# SparkFun_GPS_ZED-F9K_uHat.net
KiCad netlist of a schematic drawn in EAGLE
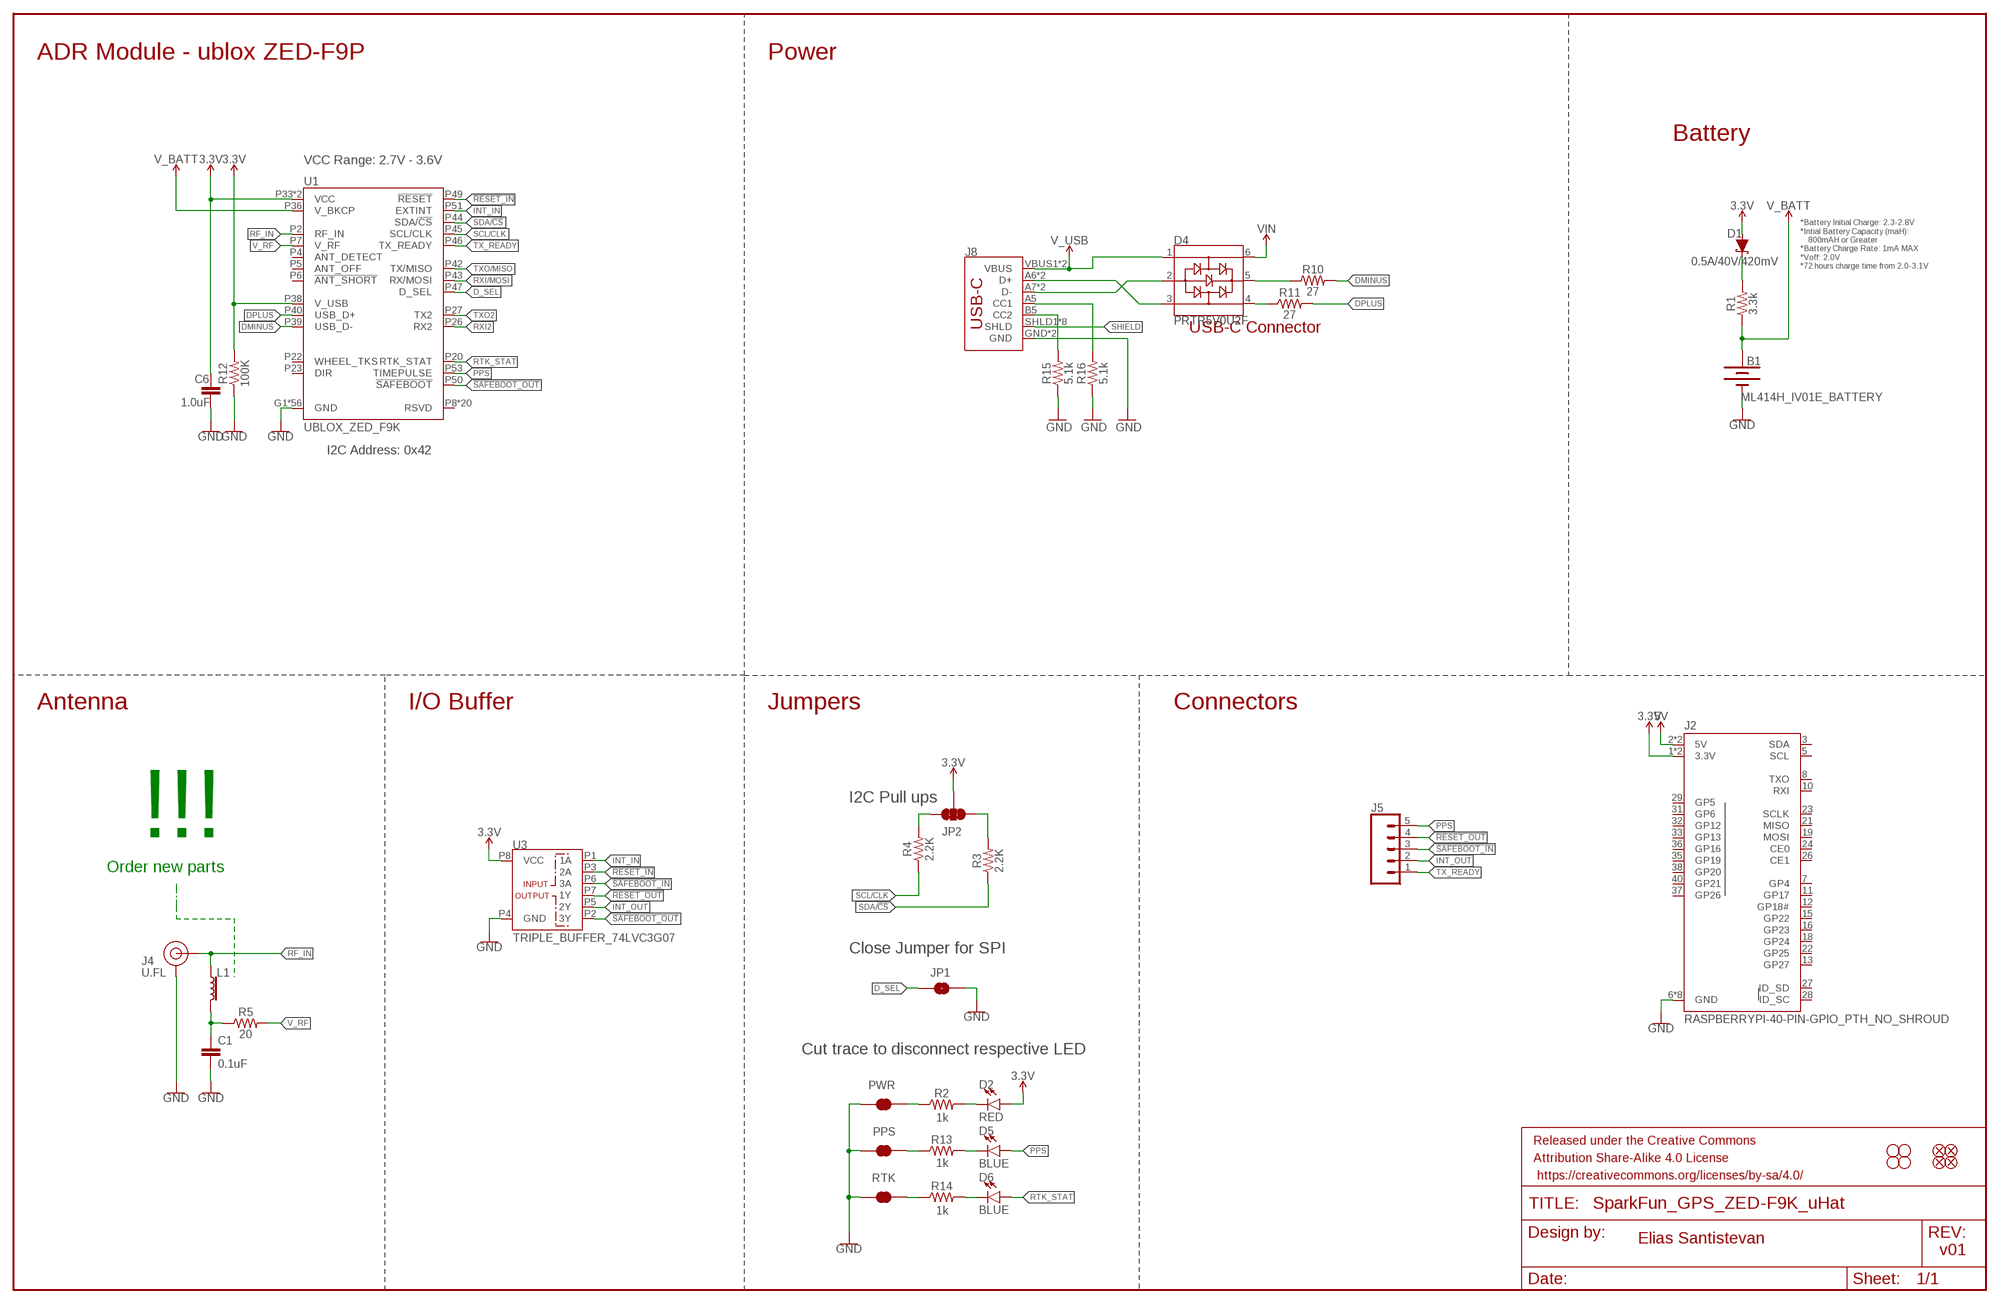
[diagram p0: schematic, sheet 1]

(export (version "E")
  (design (tool "Eeschema 10.0.6"))
  (components
    (comp (ref "B1")
      (value "ML414H_IV01E_BATTERY")
      (footprint "eagle-import:ML414H_IV01E")
      (libsource (lib "eagle-import") (part "ML414H_IV01E_BATTERY"))
    )
    (comp (ref "C1")
      (value "0.1uF")
      (footprint "eagle-import:0402")
      (libsource (lib "eagle-import") (part "0.1UF-0402-16V-10%"))
    )
    (comp (ref "C6")
      (value "1.0uF")
      (footprint "eagle-import:0402")
      (libsource (lib "eagle-import") (part "1.0UF-0402-16V-10%"))
    )
    (comp (ref "D1")
      (value "0.5A/40V/420mV")
      (footprint "eagle-import:SOD-323")
      (libsource (lib "eagle-import") (part "DIODE-SCHOTTKY-PMEG4005EJ"))
    )
    (comp (ref "D2")
      (value "RED")
      (footprint "eagle-import:LED-0603")
      (libsource (lib "eagle-import") (part "LED-RED0603"))
    )
    (comp (ref "D4")
      (value "PRTR5V0U2F")
      (footprint "eagle-import:SOT886")
      (libsource (lib "eagle-import") (part "PRTR5V0U2F"))
    )
    (comp (ref "D5")
      (value "BLUE")
      (footprint "eagle-import:LED-0603")
      (libsource (lib "eagle-import") (part "LED-BLUE0603"))
    )
    (comp (ref "D6")
      (value "BLUE")
      (footprint "eagle-import:LED-0603")
      (libsource (lib "eagle-import") (part "LED-BLUE0603"))
    )
    (comp (ref "FD9")
      (value "FIDUCIALUFIDUCIAL")
      (footprint "eagle-import:FIDUCIAL-MICRO")
      (libsource (lib "eagle-import") (part "FIDUCIALUFIDUCIAL"))
    )
    (comp (ref "FD10")
      (value "FIDUCIALUFIDUCIAL")
      (footprint "eagle-import:FIDUCIAL-MICRO")
      (libsource (lib "eagle-import") (part "FIDUCIALUFIDUCIAL"))
    )
    (comp (ref "FD11")
      (value "FIDUCIALUFIDUCIAL")
      (footprint "eagle-import:FIDUCIAL-MICRO")
      (libsource (lib "eagle-import") (part "FIDUCIALUFIDUCIAL"))
    )
    (comp (ref "FD12")
      (value "FIDUCIALUFIDUCIAL")
      (footprint "eagle-import:FIDUCIAL-MICRO")
      (libsource (lib "eagle-import") (part "FIDUCIALUFIDUCIAL"))
    )
    (comp (ref "FRAME2")
      (value "FRAME-LEDGER")
      (footprint "eagle-import:CREATIVE_COMMONS")
      (libsource (lib "eagle-import") (part "FRAME-LEDGER"))
    )
    (comp (ref "H9")
      (value "STAND-OFFTIGHT")
      (footprint "eagle-import:STAND-OFF-TIGHT")
      (libsource (lib "eagle-import") (part "STAND-OFFTIGHT"))
    )
    (comp (ref "H10")
      (value "STAND-OFFTIGHT")
      (footprint "eagle-import:STAND-OFF-TIGHT")
      (libsource (lib "eagle-import") (part "STAND-OFFTIGHT"))
    )
    (comp (ref "H11")
      (value "STAND-OFFTIGHT")
      (footprint "eagle-import:STAND-OFF-TIGHT")
      (libsource (lib "eagle-import") (part "STAND-OFFTIGHT"))
    )
    (comp (ref "H12")
      (value "STAND-OFFTIGHT")
      (footprint "eagle-import:STAND-OFF-TIGHT")
      (libsource (lib "eagle-import") (part "STAND-OFFTIGHT"))
    )
    (comp (ref "J2")
      (value "RASPBERRYPI-40-PIN-GPIO_PTH_NO_SHROUD")
      (footprint "eagle-import:2X20")
      (libsource (lib "eagle-import") (part "RASPBERRYPI-40-PIN-GPIO_PTH_NO_SHROUD"))
    )
    (comp (ref "J4")
      (value "U.FL")
      (footprint "eagle-import:U.FL")
      (libsource (lib "eagle-import") (part "U.FL2PIN"))
    )
    (comp (ref "J5")
      (value "CONN_05NO_SILK")
      (footprint "eagle-import:1X05_NO_SILK")
      (libsource (lib "eagle-import") (part "CONN_05NO_SILK"))
    )
    (comp (ref "J8")
      (value "USB_C2-LAYER")
      (footprint "eagle-import:USB-C-16P")
      (libsource (lib "eagle-import") (part "USB_C2-LAYER"))
    )
    (comp (ref "JP1")
      (value "JUMPER-SMT_2_NO_SILK")
      (footprint "eagle-import:SMT-JUMPER_2_NO_SILK")
      (libsource (lib "eagle-import") (part "JUMPER-SMT_2_NO_SILK"))
    )
    (comp (ref "JP2")
      (value "JUMPER-SMT_3_2-NC_TRACE_SILK")
      (footprint "eagle-import:SMT-JUMPER_3_2-NC_TRACE_SILK")
      (libsource (lib "eagle-import") (part "JUMPER-SMT_3_2-NC_TRACE_SILK"))
    )
    (comp (ref "L1")
      (value "3.9NH")
      (footprint "eagle-import:0402")
      (fields (field (name "MFG_PART") "BLM15HB121SN1D"))
      (libsource (lib "eagle-import") (part "FERRITE_BEAD-120_OHM-0402"))
    )
    (comp (ref "PPS")
      (value "JUMPER-SMT_2_NC_TRACE_SILK")
      (footprint "eagle-import:SMT-JUMPER_2_NC_TRACE_SILK")
      (libsource (lib "eagle-import") (part "JUMPER-SMT_2_NC_TRACE_SILK"))
    )
    (comp (ref "PWR")
      (value "JUMPER-SMT_2_NC_TRACE_SILK")
      (footprint "eagle-import:SMT-JUMPER_2_NC_TRACE_SILK")
      (libsource (lib "eagle-import") (part "JUMPER-SMT_2_NC_TRACE_SILK"))
    )
    (comp (ref "R1")
      (value "3.3k")
      (footprint "eagle-import:0603")
      (libsource (lib "eagle-import") (part "3.3KOHM-0603-1/10W-1%"))
    )
    (comp (ref "R2")
      (value "1KOHM-0402-1/16W-1%")
      (footprint "eagle-import:0402")
      (libsource (lib "eagle-import") (part "1KOHM-0402-1/16W-1%"))
    )
    (comp (ref "R3")
      (value "2.2K")
      (footprint "eagle-import:0402")
      (libsource (lib "eagle-import") (part "2.2KOHM-0402-1/16W-1%"))
    )
    (comp (ref "R4")
      (value "2.2K")
      (footprint "eagle-import:0402")
      (libsource (lib "eagle-import") (part "2.2KOHM-0402-1/16W-1%"))
    )
    (comp (ref "R5")
      (value "20")
      (footprint "eagle-import:0603")
      (libsource (lib "eagle-import") (part "20OHM-0603-1/10W-1%"))
    )
    (comp (ref "R10")
      (value "27")
      (footprint "eagle-import:0603")
      (libsource (lib "eagle-import") (part "27OHM-0603-1/10W-1%"))
    )
    (comp (ref "R11")
      (value "27")
      (footprint "eagle-import:0603")
      (libsource (lib "eagle-import") (part "27OHM-0603-1/10W-1%"))
    )
    (comp (ref "R12")
      (value "100K")
      (footprint "eagle-import:0402")
      (libsource (lib "eagle-import") (part "100KOHM-0402-1/16W-1%"))
    )
    (comp (ref "R13")
      (value "1KOHM-0402-1/16W-1%")
      (footprint "eagle-import:0402")
      (libsource (lib "eagle-import") (part "1KOHM-0402-1/16W-1%"))
    )
    (comp (ref "R14")
      (value "1KOHM-0402-1/16W-1%")
      (footprint "eagle-import:0402")
      (libsource (lib "eagle-import") (part "1KOHM-0402-1/16W-1%"))
    )
    (comp (ref "R15")
      (value "5.1k")
      (footprint "eagle-import:0402")
      (libsource (lib "eagle-import") (part "5.1KOHM-0402-1/16W-1%"))
    )
    (comp (ref "R16")
      (value "5.1k")
      (footprint "eagle-import:0402")
      (libsource (lib "eagle-import") (part "5.1KOHM-0402-1/16W-1%"))
    )
    (comp (ref "RTK")
      (value "JUMPER-SMT_2_NC_TRACE_SILK")
      (footprint "eagle-import:SMT-JUMPER_2_NC_TRACE_SILK")
      (libsource (lib "eagle-import") (part "JUMPER-SMT_2_NC_TRACE_SILK"))
    )
    (comp (ref "U1")
      (value "UBLOX_ZED_F9K")
      (footprint "eagle-import:UBLOX_ZED_F9K")
      (libsource (lib "eagle-import") (part "UBLOX_ZED_F9K"))
    )
    (comp (ref "U3")
      (value "TRIPLE_BUFFER_74LVC3G07")
      (footprint "eagle-import:SOP_8-PIN")
      (libsource (lib "eagle-import") (part "TRIPLE_BUFFER_74LVC3G07"))
    )
  )
  (nets
    (net (code "1") (name "/SDA{slash}~{CS}") (class "Default")
      (node (ref "R3") (pin "1") (pinfunction "1_1") (pintype "passive"))
      (node (ref "U1") (pin "P44") (pinfunction "SDA/~{CS}_P44") (pintype "bidirectional"))
    )
    (net (code "2") (name "/~{RESET_IN}") (class "Default")
      (node (ref "U1") (pin "P49") (pinfunction "~{RESET}_P49") (pintype "bidirectional"))
      (node (ref "U3") (pin "P3") (pinfunction "2A_P3") (pintype "bidirectional"))
    )
    (net (code "3") (name "/~{RESET_OUT}") (class "Default")
      (node (ref "J5") (pin "4") (pinfunction "4_4") (pintype "passive"))
      (node (ref "U3") (pin "P7") (pinfunction "1Y_P7") (pintype "bidirectional"))
    )
    (net (code "4") (name "/~{SAFEBOOT_IN}") (class "Default")
      (node (ref "J5") (pin "3") (pinfunction "3_3") (pintype "passive"))
      (node (ref "U3") (pin "P6") (pinfunction "3A_P6") (pintype "bidirectional"))
    )
    (net (code "5") (name "/~{SAFEBOOT_OUT}") (class "Default")
      (node (ref "U1") (pin "P50") (pinfunction "~{SAFEBOOT}_P50") (pintype "input"))
      (node (ref "U3") (pin "P2") (pinfunction "3Y_P2") (pintype "bidirectional"))
    )
    (net (code "6") (name "3.3V") (class "Default")
      (node (ref "C6") (pin "1") (pinfunction "1_1") (pintype "passive"))
      (node (ref "D1") (pin "A") (pinfunction "A_A") (pintype "passive"))
      (node (ref "D2") (pin "A") (pinfunction "A_A") (pintype "passive"))
      (node (ref "J2") (pin "1") (pinfunction "3.3V_1") (pintype "power_in"))
      (node (ref "J2") (pin "17") (pinfunction "3.3V_17") (pintype "power_in"))
      (node (ref "JP2") (pin "2") (pinfunction "2_2") (pintype "passive"))
      (node (ref "R12") (pin "2") (pinfunction "2_2") (pintype "passive"))
      (node (ref "U1") (pin "P33") (pinfunction "VCC_P33") (pintype "power_in"))
      (node (ref "U1") (pin "P34") (pinfunction "VCC_P34") (pintype "power_in"))
      (node (ref "U1") (pin "P38") (pinfunction "V_USB_P38") (pintype "power_in"))
      (node (ref "U3") (pin "P8") (pinfunction "VCC_P8") (pintype "power_in"))
    )
    (net (code "7") (name "5V") (class "Default")
      (node (ref "J2") (pin "2") (pinfunction "5V_2") (pintype "power_in"))
      (node (ref "J2") (pin "4") (pinfunction "5V_4") (pintype "power_in"))
    )
    (net (code "8") (name "DMINUS") (class "Default")
      (node (ref "R10") (pin "2") (pinfunction "2_2") (pintype "passive"))
      (node (ref "U1") (pin "P39") (pinfunction "USB_D-_P39") (pintype "bidirectional"))
    )
    (net (code "9") (name "DPLUS") (class "Default")
      (node (ref "R11") (pin "2") (pinfunction "2_2") (pintype "passive"))
      (node (ref "U1") (pin "P40") (pinfunction "USB_D+_P40") (pintype "bidirectional"))
    )
    (net (code "10") (name "D_SEL") (class "Default")
      (node (ref "JP1") (pin "1") (pinfunction "1_1") (pintype "passive"))
      (node (ref "U1") (pin "P47") (pinfunction "D_SEL_P47") (pintype "bidirectional"))
    )
    (net (code "11") (name "GND") (class "Default")
      (node (ref "B1") (pin "-") (pinfunction "-_-") (pintype "power_in"))
      (node (ref "C1") (pin "2") (pinfunction "2_2") (pintype "passive"))
      (node (ref "C6") (pin "2") (pinfunction "2_2") (pintype "passive"))
      (node (ref "J2") (pin "14") (pinfunction "GND_14") (pintype "power_in"))
      (node (ref "J2") (pin "20") (pinfunction "GND_20") (pintype "power_in"))
      (node (ref "J2") (pin "25") (pinfunction "GND_25") (pintype "power_in"))
      (node (ref "J2") (pin "30") (pinfunction "GND_30") (pintype "power_in"))
      (node (ref "J2") (pin "34") (pinfunction "GND_34") (pintype "power_in"))
      (node (ref "J2") (pin "39") (pinfunction "GND_39") (pintype "power_in"))
      (node (ref "J2") (pin "6") (pinfunction "GND_6") (pintype "power_in"))
      (node (ref "J2") (pin "9") (pinfunction "GND_9") (pintype "power_in"))
      (node (ref "J4") (pin "1") (pinfunction "GND_1") (pintype "bidirectional"))
      (node (ref "J4") (pin "2") (pinfunction "GND_2") (pintype "bidirectional"))
      (node (ref "J8") (pin "GND") (pinfunction "GND_GND") (pintype "bidirectional"))
      (node (ref "J8") (pin "GND2") (pinfunction "GND_GND2") (pintype "bidirectional"))
      (node (ref "JP1") (pin "2") (pinfunction "2_2") (pintype "passive"))
      (node (ref "PPS") (pin "1") (pinfunction "1_1") (pintype "passive"))
      (node (ref "PWR") (pin "1") (pinfunction "1_1") (pintype "passive"))
      (node (ref "R12") (pin "1") (pinfunction "1_1") (pintype "passive"))
      (node (ref "R15") (pin "1") (pinfunction "1_1") (pintype "passive"))
      (node (ref "R16") (pin "1") (pinfunction "1_1") (pintype "passive"))
      (node (ref "RTK") (pin "1") (pinfunction "1_1") (pintype "passive"))
      (node (ref "U1") (pin "G1") (pinfunction "GND_G1") (pintype "power_in"))
      (node (ref "U1") (pin "G10") (pinfunction "GND_G10") (pintype "power_in"))
      (node (ref "U1") (pin "G11") (pinfunction "GND_G11") (pintype "power_in"))
      (node (ref "U1") (pin "G12") (pinfunction "GND_G12") (pintype "power_in"))
      (node (ref "U1") (pin "G13") (pinfunction "GND_G13") (pintype "power_in"))
      (node (ref "U1") (pin "G14") (pinfunction "GND_G14") (pintype "power_in"))
      (node (ref "U1") (pin "G15") (pinfunction "GND_G15") (pintype "power_in"))
      (node (ref "U1") (pin "G16") (pinfunction "GND_G16") (pintype "power_in"))
      (node (ref "U1") (pin "G17") (pinfunction "GND_G17") (pintype "power_in"))
      (node (ref "U1") (pin "G18") (pinfunction "GND_G18") (pintype "power_in"))
      (node (ref "U1") (pin "G19") (pinfunction "GND_G19") (pintype "power_in"))
      (node (ref "U1") (pin "G2") (pinfunction "GND_G2") (pintype "power_in"))
      (node (ref "U1") (pin "G20") (pinfunction "GND_G20") (pintype "power_in"))
      (node (ref "U1") (pin "G21") (pinfunction "GND_G21") (pintype "power_in"))
      (node (ref "U1") (pin "G22") (pinfunction "GND_G22") (pintype "power_in"))
      (node (ref "U1") (pin "G23") (pinfunction "GND_G23") (pintype "power_in"))
      (node (ref "U1") (pin "G24") (pinfunction "GND_G24") (pintype "power_in"))
      (node (ref "U1") (pin "G25") (pinfunction "GND_G25") (pintype "power_in"))
      (node (ref "U1") (pin "G26") (pinfunction "GND_G26") (pintype "power_in"))
      (node (ref "U1") (pin "G27") (pinfunction "GND_G27") (pintype "power_in"))
      (node (ref "U1") (pin "G28") (pinfunction "GND_G28") (pintype "power_in"))
      (node (ref "U1") (pin "G29") (pinfunction "GND_G29") (pintype "power_in"))
      (node (ref "U1") (pin "G3") (pinfunction "GND_G3") (pintype "power_in"))
      (node (ref "U1") (pin "G30") (pinfunction "GND_G30") (pintype "power_in"))
      (node (ref "U1") (pin "G31") (pinfunction "GND_G31") (pintype "power_in"))
      (node (ref "U1") (pin "G32") (pinfunction "GND_G32") (pintype "power_in"))
      (node (ref "U1") (pin "G33") (pinfunction "GND_G33") (pintype "power_in"))
      (node (ref "U1") (pin "G34") (pinfunction "GND_G34") (pintype "power_in"))
      (node (ref "U1") (pin "G35") (pinfunction "GND_G35") (pintype "power_in"))
      (node (ref "U1") (pin "G36") (pinfunction "GND_G36") (pintype "power_in"))
      (node (ref "U1") (pin "G37") (pinfunction "GND_G37") (pintype "power_in"))
      (node (ref "U1") (pin "G38") (pinfunction "GND_G38") (pintype "power_in"))
      (node (ref "U1") (pin "G39") (pinfunction "GND_G39") (pintype "power_in"))
      (node (ref "U1") (pin "G4") (pinfunction "GND_G4") (pintype "power_in"))
      (node (ref "U1") (pin "G40") (pinfunction "GND_G40") (pintype "power_in"))
      (node (ref "U1") (pin "G41") (pinfunction "GND_G41") (pintype "power_in"))
      (node (ref "U1") (pin "G42") (pinfunction "GND_G42") (pintype "power_in"))
      (node (ref "U1") (pin "G43") (pinfunction "GND_G43") (pintype "power_in"))
      (node (ref "U1") (pin "G44") (pinfunction "GND_G44") (pintype "power_in"))
      (node (ref "U1") (pin "G45") (pinfunction "GND_G45") (pintype "power_in"))
      (node (ref "U1") (pin "G46") (pinfunction "GND_G46") (pintype "power_in"))
      (node (ref "U1") (pin "G47") (pinfunction "GND_G47") (pintype "power_in"))
      (node (ref "U1") (pin "G48") (pinfunction "GND_G48") (pintype "power_in"))
      (node (ref "U1") (pin "G5") (pinfunction "GND_G5") (pintype "power_in"))
      (node (ref "U1") (pin "G6") (pinfunction "GND_G6") (pintype "power_in"))
      (node (ref "U1") (pin "G7") (pinfunction "GND_G7") (pintype "power_in"))
      (node (ref "U1") (pin "G8") (pinfunction "GND_G8") (pintype "power_in"))
      (node (ref "U1") (pin "G9") (pinfunction "GND_G9") (pintype "power_in"))
      (node (ref "U1") (pin "P1") (pinfunction "GND_P1") (pintype "power_in"))
      (node (ref "U1") (pin "P12") (pinfunction "GND_P12") (pintype "power_in"))
      (node (ref "U1") (pin "P14") (pinfunction "GND_P14") (pintype "power_in"))
      (node (ref "U1") (pin "P3") (pinfunction "GND_P3") (pintype "power_in"))
      (node (ref "U1") (pin "P32") (pinfunction "GND_P32") (pintype "power_in"))
      (node (ref "U1") (pin "P37") (pinfunction "GND_P37") (pintype "power_in"))
      (node (ref "U1") (pin "P41") (pinfunction "GND_P41") (pintype "power_in"))
      (node (ref "U1") (pin "P48") (pinfunction "GND_P48") (pintype "power_in"))
      (node (ref "U3") (pin "P4") (pinfunction "GND_P4") (pintype "power_in"))
    )
    (net (code "12") (name "INT_IN") (class "Default")
      (node (ref "U1") (pin "P51") (pinfunction "EXTINT_P51") (pintype "bidirectional"))
      (node (ref "U3") (pin "P1") (pinfunction "1A_P1") (pintype "bidirectional"))
    )
    (net (code "13") (name "INT_OUT") (class "Default")
      (node (ref "J5") (pin "2") (pinfunction "2_2") (pintype "passive"))
      (node (ref "U3") (pin "P5") (pinfunction "2Y_P5") (pintype "bidirectional"))
    )
    (net (code "14") (name "Net-(C1-Pad1)") (class "Default")
      (node (ref "C1") (pin "1") (pinfunction "1_1") (pintype "passive"))
      (node (ref "L1") (pin "2") (pinfunction "2_2") (pintype "passive"))
      (node (ref "R5") (pin "1") (pinfunction "1_1") (pintype "passive"))
    )
    (net (code "15") (name "Net-(D1-PadC)") (class "Default")
      (node (ref "D1") (pin "C") (pinfunction "C_C") (pintype "passive"))
      (node (ref "R1") (pin "2") (pinfunction "2_2") (pintype "passive"))
    )
    (net (code "16") (name "Net-(D2-PadC)") (class "Default")
      (node (ref "D2") (pin "C") (pinfunction "C_C") (pintype "passive"))
      (node (ref "R2") (pin "2") (pinfunction "2_2") (pintype "passive"))
    )
    (net (code "17") (name "Net-(D4-Pad2)") (class "Default")
      (node (ref "D4") (pin "2") (pinfunction "2_2") (pintype "bidirectional"))
      (node (ref "J8") (pin "A7") (pinfunction "D-_A7") (pintype "bidirectional"))
      (node (ref "J8") (pin "B7") (pinfunction "D-_B7") (pintype "bidirectional"))
    )
    (net (code "18") (name "Net-(D4-Pad3)") (class "Default")
      (node (ref "D4") (pin "3") (pinfunction "3_3") (pintype "bidirectional"))
      (node (ref "J8") (pin "A6") (pinfunction "D+_A6") (pintype "bidirectional"))
      (node (ref "J8") (pin "B6") (pinfunction "D+_B6") (pintype "bidirectional"))
    )
    (net (code "19") (name "Net-(D4-Pad4)") (class "Default")
      (node (ref "D4") (pin "4") (pinfunction "4_4") (pintype "bidirectional"))
      (node (ref "R11") (pin "1") (pinfunction "1_1") (pintype "passive"))
    )
    (net (code "20") (name "Net-(D4-Pad5)") (class "Default")
      (node (ref "D4") (pin "5") (pinfunction "5_5") (pintype "bidirectional"))
      (node (ref "R10") (pin "1") (pinfunction "1_1") (pintype "passive"))
    )
    (net (code "21") (name "Net-(D5-PadC)") (class "Default")
      (node (ref "D5") (pin "C") (pinfunction "C_C") (pintype "passive"))
      (node (ref "R13") (pin "2") (pinfunction "2_2") (pintype "passive"))
    )
    (net (code "22") (name "Net-(D6-PadC)") (class "Default")
      (node (ref "D6") (pin "C") (pinfunction "C_C") (pintype "passive"))
      (node (ref "R14") (pin "2") (pinfunction "2_2") (pintype "passive"))
    )
    (net (code "23") (name "Net-(J8-CC1)") (class "Default")
      (node (ref "J8") (pin "A5") (pinfunction "CC1_A5") (pintype "bidirectional"))
      (node (ref "R16") (pin "2") (pinfunction "2_2") (pintype "passive"))
    )
    (net (code "24") (name "Net-(J8-CC2)") (class "Default")
      (node (ref "J8") (pin "B5") (pinfunction "CC2_B5") (pintype "bidirectional"))
      (node (ref "R15") (pin "2") (pinfunction "2_2") (pintype "passive"))
    )
    (net (code "25") (name "Net-(JP2-Pad1)") (class "Default")
      (node (ref "JP2") (pin "1") (pinfunction "1_1") (pintype "passive"))
      (node (ref "R3") (pin "2") (pinfunction "2_2") (pintype "passive"))
    )
    (net (code "26") (name "Net-(JP2-Pad3)") (class "Default")
      (node (ref "JP2") (pin "3") (pinfunction "3_3") (pintype "passive"))
      (node (ref "R4") (pin "2") (pinfunction "2_2") (pintype "passive"))
    )
    (net (code "27") (name "Net-(PPS-Pad2)") (class "Default")
      (node (ref "PPS") (pin "2") (pinfunction "2_2") (pintype "passive"))
      (node (ref "R13") (pin "1") (pinfunction "1_1") (pintype "passive"))
    )
    (net (code "28") (name "Net-(PWR-Pad2)") (class "Default")
      (node (ref "PWR") (pin "2") (pinfunction "2_2") (pintype "passive"))
      (node (ref "R2") (pin "1") (pinfunction "1_1") (pintype "passive"))
    )
    (net (code "29") (name "Net-(R14-Pad1)") (class "Default")
      (node (ref "R14") (pin "1") (pinfunction "1_1") (pintype "passive"))
      (node (ref "RTK") (pin "2") (pinfunction "2_2") (pintype "passive"))
    )
    (net (code "30") (name "PPS") (class "Default")
      (node (ref "D5") (pin "A") (pinfunction "A_A") (pintype "passive"))
      (node (ref "J5") (pin "5") (pinfunction "5_5") (pintype "passive"))
      (node (ref "U1") (pin "P53") (pinfunction "TIMEPULSE_P53") (pintype "output"))
    )
    (net (code "31") (name "RF_IN") (class "Default")
      (node (ref "J4") (pin "FEED") (pinfunction "SIGNAL_FEED") (pintype "bidirectional"))
      (node (ref "L1") (pin "1") (pinfunction "1_1") (pintype "passive"))
      (node (ref "U1") (pin "P2") (pinfunction "RF_IN_P2") (pintype "input"))
    )
    (net (code "32") (name "RTK_STAT") (class "Default")
      (node (ref "D6") (pin "A") (pinfunction "A_A") (pintype "passive"))
      (node (ref "U1") (pin "P20") (pinfunction "RTK_STAT_P20") (pintype "output"))
    )
    (net (code "33") (name "RXI2") (class "Default")
      (node (ref "U1") (pin "P26") (pinfunction "RX2_P26") (pintype "input"))
    )
    (net (code "34") (name "RXI{slash}MOSI") (class "Default")
      (node (ref "U1") (pin "P43") (pinfunction "RX/MOSI_P43") (pintype "bidirectional"))
    )
    (net (code "35") (name "SCL{slash}CLK") (class "Default")
      (node (ref "R4") (pin "1") (pinfunction "1_1") (pintype "passive"))
      (node (ref "U1") (pin "P45") (pinfunction "SCL/CLK_P45") (pintype "bidirectional"))
    )
    (net (code "36") (name "SHIELD") (class "Default")
      (node (ref "J8") (pin "SHLD1") (pinfunction "SHLD_SHLD1") (pintype "bidirectional"))
      (node (ref "J8") (pin "SHLD2") (pinfunction "SHLD_SHLD2") (pintype "bidirectional"))
      (node (ref "J8") (pin "SHLD3") (pinfunction "SHLD_SHLD3") (pintype "bidirectional"))
      (node (ref "J8") (pin "SHLD4") (pinfunction "SHLD_SHLD4") (pintype "bidirectional"))
      (node (ref "J8") (pin "SHLD5") (pinfunction "SHLD_SHLD5") (pintype "bidirectional"))
      (node (ref "J8") (pin "SHLD6") (pinfunction "SHLD_SHLD6") (pintype "bidirectional"))
      (node (ref "J8") (pin "SHLD7") (pinfunction "SHLD_SHLD7") (pintype "bidirectional"))
      (node (ref "J8") (pin "SHLD8") (pinfunction "SHLD_SHLD8") (pintype "bidirectional"))
    )
    (net (code "37") (name "TXO2") (class "Default")
      (node (ref "U1") (pin "P27") (pinfunction "TX2_P27") (pintype "output"))
    )
    (net (code "38") (name "TXO{slash}MISO") (class "Default")
      (node (ref "U1") (pin "P42") (pinfunction "TX/MISO_P42") (pintype "bidirectional"))
    )
    (net (code "39") (name "TX_READY") (class "Default")
      (node (ref "J5") (pin "1") (pinfunction "1_1") (pintype "passive"))
      (node (ref "U1") (pin "P46") (pinfunction "TX_READY_P46") (pintype "bidirectional"))
    )
    (net (code "40") (name "VIN") (class "Default")
      (node (ref "D4") (pin "6") (pinfunction "6_6") (pintype "bidirectional"))
    )
    (net (code "41") (name "V_BATT") (class "Default")
      (node (ref "B1") (pin "+") (pinfunction "+_+") (pintype "power_in"))
      (node (ref "R1") (pin "1") (pinfunction "1_1") (pintype "passive"))
      (node (ref "U1") (pin "P36") (pinfunction "V_BKCP_P36") (pintype "power_in"))
    )
    (net (code "42") (name "V_RF") (class "Default")
      (node (ref "R5") (pin "2") (pinfunction "2_2") (pintype "passive"))
      (node (ref "U1") (pin "P7") (pinfunction "V_RF_P7") (pintype "output"))
    )
    (net (code "43") (name "V_USB") (class "Default")
      (node (ref "D4") (pin "1") (pinfunction "1_1") (pintype "bidirectional"))
      (node (ref "J8") (pin "VBUS1") (pinfunction "VBUS_VBUS1") (pintype "bidirectional"))
      (node (ref "J8") (pin "VBUS2") (pinfunction "VBUS_VBUS2") (pintype "bidirectional"))
    )
    (net (code "44") (name "unconnected-(J2-CE0-Pad24)") (class "Default")
      (node (ref "J2") (pin "24") (pinfunction "CE0_24") (pintype "output"))
    )
    (net (code "45") (name "unconnected-(J2-CE1-Pad26)") (class "Default")
      (node (ref "J2") (pin "26") (pinfunction "CE1_26") (pintype "output"))
    )
    (net (code "46") (name "unconnected-(J2-GP4-Pad7)") (class "Default")
      (node (ref "J2") (pin "7") (pinfunction "GP4_7") (pintype "bidirectional"))
    )
    (net (code "47") (name "unconnected-(J2-GP5-Pad29)") (class "Default")
      (node (ref "J2") (pin "29") (pinfunction "GP5_29") (pintype "bidirectional"))
    )
    (net (code "48") (name "unconnected-(J2-GP6-Pad31)") (class "Default")
      (node (ref "J2") (pin "31") (pinfunction "GP6_31") (pintype "bidirectional"))
    )
    (net (code "49") (name "unconnected-(J2-GP12-Pad32)") (class "Default")
      (node (ref "J2") (pin "32") (pinfunction "GP12_32") (pintype "bidirectional"))
    )
    (net (code "50") (name "unconnected-(J2-GP13-Pad33)") (class "Default")
      (node (ref "J2") (pin "33") (pinfunction "GP13_33") (pintype "bidirectional"))
    )
    (net (code "51") (name "unconnected-(J2-GP16-Pad36)") (class "Default")
      (node (ref "J2") (pin "36") (pinfunction "GP16_36") (pintype "bidirectional"))
    )
    (net (code "52") (name "unconnected-(J2-GP17-Pad11)") (class "Default")
      (node (ref "J2") (pin "11") (pinfunction "GP17_11") (pintype "bidirectional"))
    )
    (net (code "53") (name "unconnected-(J2-GP18#-Pad12)") (class "Default")
      (node (ref "J2") (pin "12") (pinfunction "GP18#_12") (pintype "bidirectional"))
    )
    (net (code "54") (name "unconnected-(J2-GP19-Pad35)") (class "Default")
      (node (ref "J2") (pin "35") (pinfunction "GP19_35") (pintype "bidirectional"))
    )
    (net (code "55") (name "unconnected-(J2-GP20-Pad38)") (class "Default")
      (node (ref "J2") (pin "38") (pinfunction "GP20_38") (pintype "bidirectional"))
    )
    (net (code "56") (name "unconnected-(J2-GP21-Pad40)") (class "Default")
      (node (ref "J2") (pin "40") (pinfunction "GP21_40") (pintype "bidirectional"))
    )
    (net (code "57") (name "unconnected-(J2-GP22-Pad15)") (class "Default")
      (node (ref "J2") (pin "15") (pinfunction "GP22_15") (pintype "bidirectional"))
    )
    (net (code "58") (name "unconnected-(J2-GP23-Pad16)") (class "Default")
      (node (ref "J2") (pin "16") (pinfunction "GP23_16") (pintype "bidirectional"))
    )
    (net (code "59") (name "unconnected-(J2-GP24-Pad18)") (class "Default")
      (node (ref "J2") (pin "18") (pinfunction "GP24_18") (pintype "bidirectional"))
    )
    (net (code "60") (name "unconnected-(J2-GP25-Pad22)") (class "Default")
      (node (ref "J2") (pin "22") (pinfunction "GP25_22") (pintype "bidirectional"))
    )
    (net (code "61") (name "unconnected-(J2-GP26-Pad37)") (class "Default")
      (node (ref "J2") (pin "37") (pinfunction "GP26_37") (pintype "bidirectional"))
    )
    (net (code "62") (name "unconnected-(J2-GP27-Pad13)") (class "Default")
      (node (ref "J2") (pin "13") (pinfunction "GP27_13") (pintype "bidirectional"))
    )
    (net (code "63") (name "unconnected-(J2-ID_SC-Pad28)") (class "Default")
      (node (ref "J2") (pin "28") (pinfunction "ID_SC_28") (pintype "bidirectional"))
    )
    (net (code "64") (name "unconnected-(J2-ID_SD-Pad27)") (class "Default")
      (node (ref "J2") (pin "27") (pinfunction "ID_SD_27") (pintype "bidirectional"))
    )
    (net (code "65") (name "unconnected-(J2-MISO-Pad21)") (class "Default")
      (node (ref "J2") (pin "21") (pinfunction "MISO_21") (pintype "input"))
    )
    (net (code "66") (name "unconnected-(J2-MOSI-Pad19)") (class "Default")
      (node (ref "J2") (pin "19") (pinfunction "MOSI_19") (pintype "output"))
    )
    (net (code "67") (name "unconnected-(J2-RXI-Pad10)") (class "Default")
      (node (ref "J2") (pin "10") (pinfunction "RXI_10") (pintype "input"))
    )
    (net (code "68") (name "unconnected-(J2-SCL-Pad5)") (class "Default")
      (node (ref "J2") (pin "5") (pinfunction "SCL_5") (pintype "bidirectional"))
    )
    (net (code "69") (name "unconnected-(J2-SCLK-Pad23)") (class "Default")
      (node (ref "J2") (pin "23") (pinfunction "SCLK_23") (pintype "output"))
    )
    (net (code "70") (name "unconnected-(J2-SDA-Pad3)") (class "Default")
      (node (ref "J2") (pin "3") (pinfunction "SDA_3") (pintype "bidirectional"))
    )
    (net (code "71") (name "unconnected-(J2-TXO-Pad8)") (class "Default")
      (node (ref "J2") (pin "8") (pinfunction "TXO_8") (pintype "output"))
    )
    (net (code "72") (name "unconnected-(U1-ANT_DETECT-PadP4)") (class "Default")
      (node (ref "U1") (pin "P4") (pinfunction "ANT_DETECT_P4") (pintype "input"))
    )
    (net (code "73") (name "unconnected-(U1-ANT_OFF-PadP5)") (class "Default")
      (node (ref "U1") (pin "P5") (pinfunction "ANT_OFF_P5") (pintype "output"))
    )
    (net (code "74") (name "unconnected-(U1-DIR-PadP23)") (class "Default")
      (node (ref "U1") (pin "P23") (pinfunction "DIR_P23") (pintype "input"))
    )
    (net (code "75") (name "unconnected-(U1-RSVD-PadP8)") (class "Default")
      (node (ref "U1") (pin "P8") (pinfunction "RSVD_P8") (pintype "no_connect"))
    )
    (net (code "76") (name "unconnected-(U1-RSVD-PadP9)") (class "Default")
      (node (ref "U1") (pin "P9") (pinfunction "RSVD_P9") (pintype "no_connect"))
    )
    (net (code "77") (name "unconnected-(U1-RSVD-PadP10)") (class "Default")
      (node (ref "U1") (pin "P10") (pinfunction "RSVD_P10") (pintype "no_connect"))
    )
    (net (code "78") (name "unconnected-(U1-RSVD-PadP11)") (class "Default")
      (node (ref "U1") (pin "P11") (pinfunction "RSVD_P11") (pintype "no_connect"))
    )
    (net (code "79") (name "unconnected-(U1-RSVD-PadP13)") (class "Default")
      (node (ref "U1") (pin "P13") (pinfunction "RSVD_P13") (pintype "no_connect"))
    )
    (net (code "80") (name "unconnected-(U1-RSVD-PadP15)") (class "Default")
      (node (ref "U1") (pin "P15") (pinfunction "RSVD_P15") (pintype "no_connect"))
    )
    (net (code "81") (name "unconnected-(U1-RSVD-PadP16)") (class "Default")
      (node (ref "U1") (pin "P16") (pinfunction "RSVD_P16") (pintype "no_connect"))
    )
    (net (code "82") (name "unconnected-(U1-RSVD-PadP17)") (class "Default")
      (node (ref "U1") (pin "P17") (pinfunction "RSVD_P17") (pintype "no_connect"))
    )
    (net (code "83") (name "unconnected-(U1-RSVD-PadP18)") (class "Default")
      (node (ref "U1") (pin "P18") (pinfunction "RSVD_P18") (pintype "no_connect"))
    )
    (net (code "84") (name "unconnected-(U1-RSVD-PadP19)") (class "Default")
      (node (ref "U1") (pin "P19") (pinfunction "RSVD_P19") (pintype "no_connect"))
    )
    (net (code "85") (name "unconnected-(U1-RSVD-PadP21)") (class "Default")
      (node (ref "U1") (pin "P21") (pinfunction "RSVD_P21") (pintype "no_connect"))
    )
    (net (code "86") (name "unconnected-(U1-RSVD-PadP24)") (class "Default")
      (node (ref "U1") (pin "P24") (pinfunction "RSVD_P24") (pintype "no_connect"))
    )
    (net (code "87") (name "unconnected-(U1-RSVD-PadP25)") (class "Default")
      (node (ref "U1") (pin "P25") (pinfunction "RSVD_P25") (pintype "no_connect"))
    )
    (net (code "88") (name "unconnected-(U1-RSVD-PadP28)") (class "Default")
      (node (ref "U1") (pin "P28") (pinfunction "RSVD_P28") (pintype "no_connect"))
    )
    (net (code "89") (name "unconnected-(U1-RSVD-PadP29)") (class "Default")
      (node (ref "U1") (pin "P29") (pinfunction "RSVD_P29") (pintype "no_connect"))
    )
    (net (code "90") (name "unconnected-(U1-RSVD-PadP30)") (class "Default")
      (node (ref "U1") (pin "P30") (pinfunction "RSVD_P30") (pintype "no_connect"))
    )
    (net (code "91") (name "unconnected-(U1-RSVD-PadP31)") (class "Default")
      (node (ref "U1") (pin "P31") (pinfunction "RSVD_P31") (pintype "no_connect"))
    )
    (net (code "92") (name "unconnected-(U1-RSVD-PadP35)") (class "Default")
      (node (ref "U1") (pin "P35") (pinfunction "RSVD_P35") (pintype "no_connect"))
    )
    (net (code "93") (name "unconnected-(U1-RSVD-PadP52)") (class "Default")
      (node (ref "U1") (pin "P52") (pinfunction "RSVD_P52") (pintype "no_connect"))
    )
    (net (code "94") (name "unconnected-(U1-RSVD-PadP54)") (class "Default")
      (node (ref "U1") (pin "P54") (pinfunction "RSVD_P54") (pintype "no_connect"))
    )
    (net (code "95") (name "unconnected-(U1-WHEEL_TKS-PadP22)") (class "Default")
      (node (ref "U1") (pin "P22") (pinfunction "WHEEL_TKS_P22") (pintype "input"))
    )
    (net (code "96") (name "unconnected-(U1-~{ANT_SHORT}-PadP6)") (class "Default")
      (node (ref "U1") (pin "P6") (pinfunction "~{ANT_SHORT}_P6") (pintype "output"))
    )
  )
)
